# GameIT_HSRW.net
KiCad netlist of a schematic drawn in EAGLE
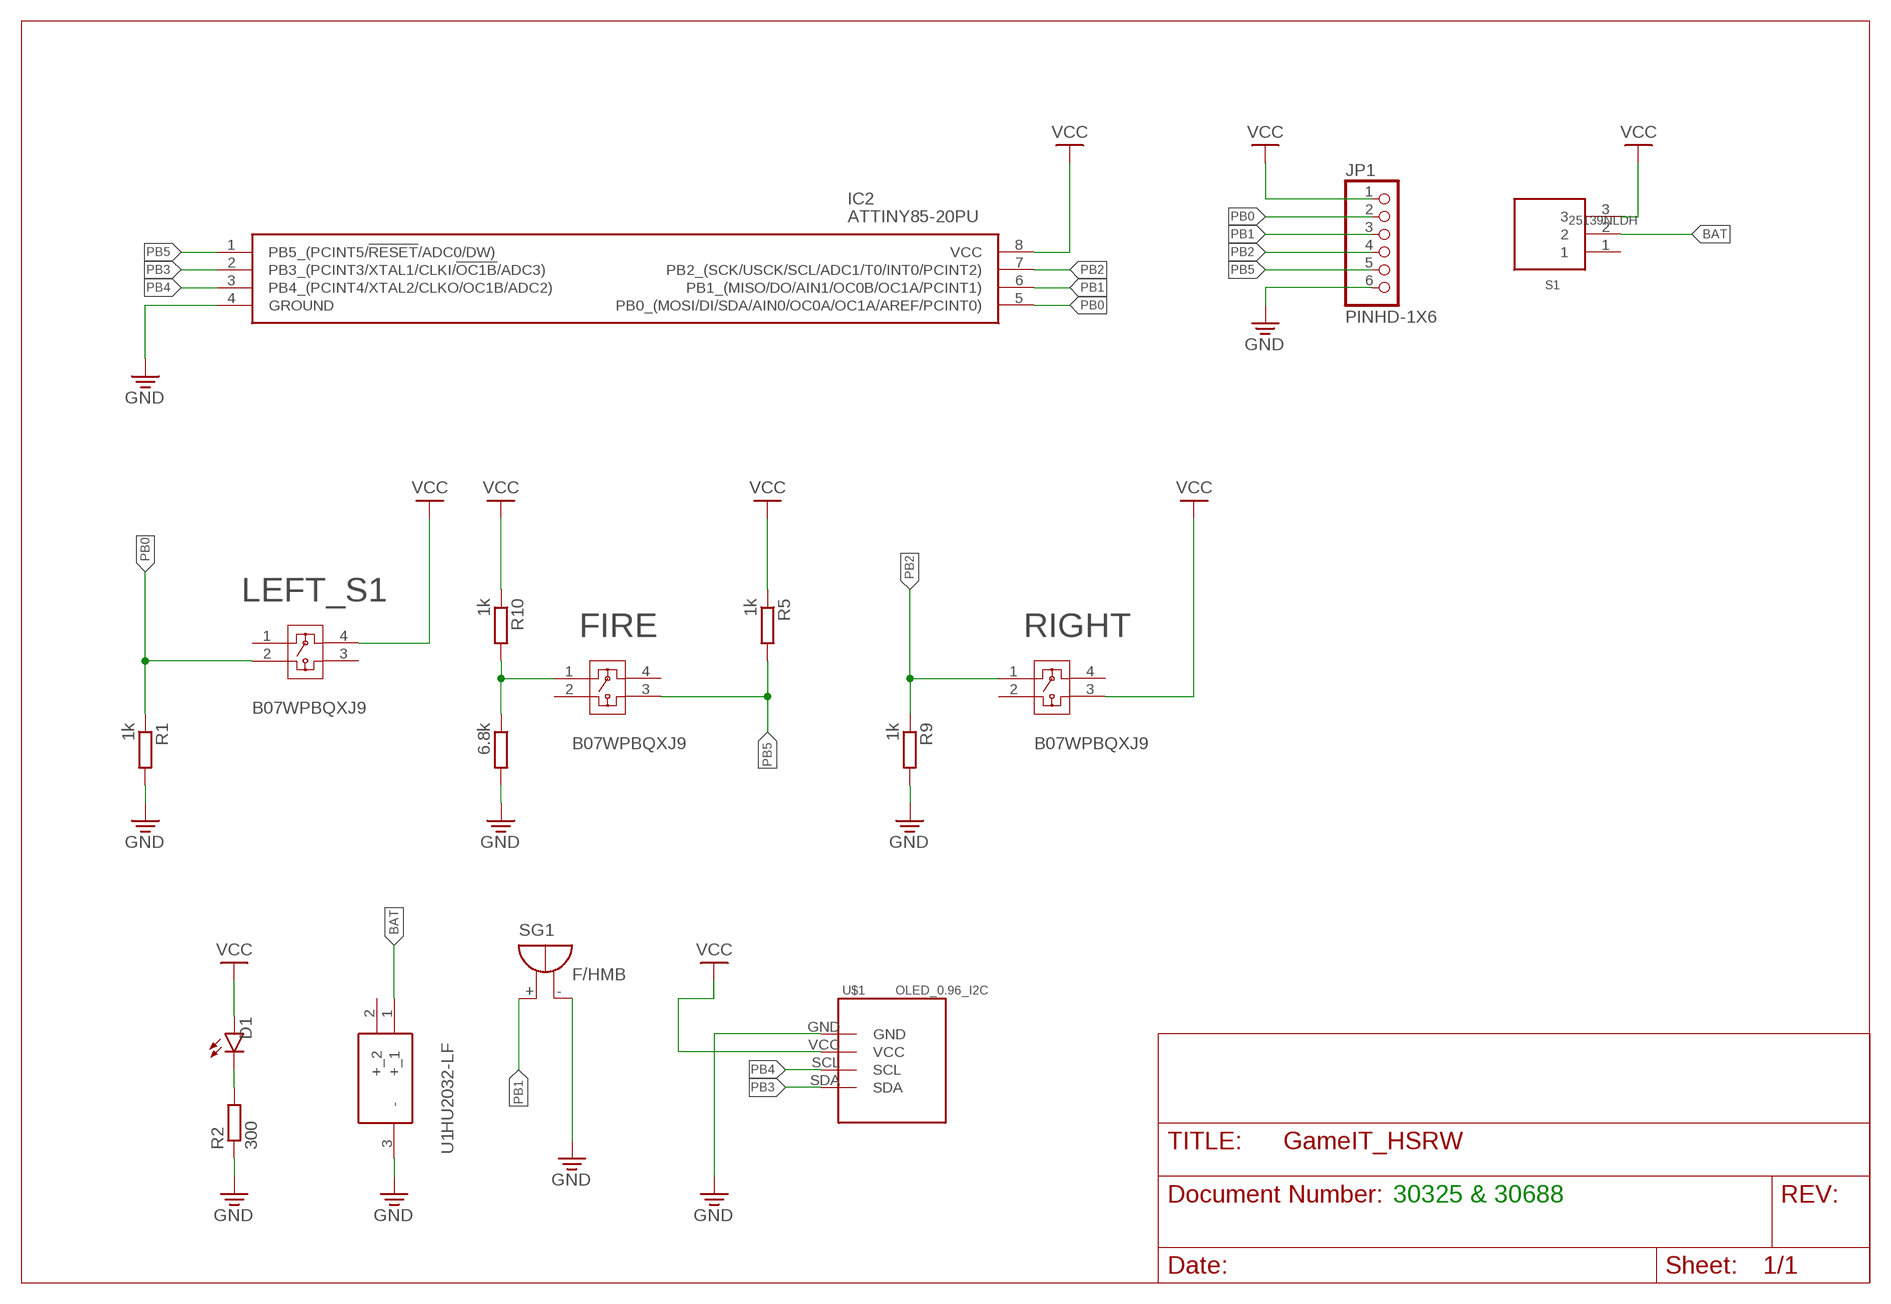
[diagram p0: schematic, sheet 1]

(export (version "E")
  (design (tool "Eeschema 10.0.6"))
  (components
    (comp (ref "D1")
      (value "LED_GREEN")
      (footprint "eagle-import:CHIPLED_1206")
      (libsource (lib "eagle-import") (part "LEDCHIPLED_1206"))
    )
    (comp (ref "FIRE")
      (value "COM-10302COM-10302_SPK")
      (footprint "eagle-import:COM-10302_SPK")
      (fields
        (field (name "MANUFACTURER_PART_NUMBER") "COM-10302")
        (field (name "COPYRIGHT") "Copyright (C) 2023 Ultra Librarian. All rights reserved.")
      )
      (libsource (lib "eagle-import") (part "COM-10302COM-10302_SPK"))
    )
    (comp (ref "IC2")
      (value "ATTINY85-20PU")
      (footprint "eagle-import:DIP781W56P254L950H533Q8N")
      (fields (field (name "MOUSER_PART_NUMBER") "556-ATTINY85-20PU"))
      (libsource (lib "eagle-import") (part "ATTINY85-20PU"))
    )
    (comp (ref "JP1")
      (value "PINHD-1X6")
      (footprint "eagle-import:1X06")
      (fields (field (name "MANUFACTURER") "Generic"))
      (libsource (lib "eagle-import") (part "PINHD-1X6"))
    )
    (comp (ref "LEFT_S1")
      (value "COM-10302COM-10302_SPK")
      (footprint "eagle-import:COM-10302_SPK")
      (fields
        (field (name "MANUFACTURER_PART_NUMBER") "COM-10302")
        (field (name "COPYRIGHT") "Copyright (C) 2023 Ultra Librarian. All rights reserved.")
      )
      (libsource (lib "eagle-import") (part "COM-10302COM-10302_SPK"))
    )
    (comp (ref "R1")
      (value "1k")
      (footprint "eagle-import:R1206")
      (libsource (lib "eagle-import") (part "R-EU_R1206"))
    )
    (comp (ref "R2")
      (value "300")
      (footprint "eagle-import:R1206")
      (libsource (lib "eagle-import") (part "R-EU_R1206"))
    )
    (comp (ref "R4")
      (value "6.8k")
      (footprint "eagle-import:R1206")
      (libsource (lib "eagle-import") (part "R-EU_R1206"))
    )
    (comp (ref "R5")
      (value "1k")
      (footprint "eagle-import:R1206")
      (libsource (lib "eagle-import") (part "R-EU_R1206"))
    )
    (comp (ref "R9")
      (value "1k")
      (footprint "eagle-import:R1206")
      (libsource (lib "eagle-import") (part "R-EU_R1206"))
    )
    (comp (ref "R10")
      (value "1k")
      (footprint "eagle-import:R1206")
      (libsource (lib "eagle-import") (part "R-EU_R1206"))
    )
    (comp (ref "RIGHT")
      (value "COM-10302COM-10302_SPK")
      (footprint "eagle-import:COM-10302_SPK")
      (fields
        (field (name "MANUFACTURER_PART_NUMBER") "COM-10302")
        (field (name "COPYRIGHT") "Copyright (C) 2023 Ultra Librarian. All rights reserved.")
      )
      (libsource (lib "eagle-import") (part "COM-10302COM-10302_SPK"))
    )
    (comp (ref "S1")
      (value "25139NLDH")
      (footprint "eagle-import:25139NLDH")
      (fields (field (name "MOUSER_PART_NUMBER") "642-25139NLDH"))
      (libsource (lib "eagle-import") (part "25139NLDH"))
    )
    (comp (ref "SG1")
      (value "F/HMB")
      (footprint "eagle-import:F_HMB")
      (libsource (lib "eagle-import") (part "F/HMB"))
    )
    (comp (ref "U$1")
      (value "OLED_0.96_I2C")
      (footprint "eagle-import:OLED_0.96_I2C")
      (libsource (lib "eagle-import") (part "OLED_0.96_I2C"))
    )
    (comp (ref "U1")
      (value "HU2032-LF")
      (footprint "eagle-import:HU2032LF")
      (fields (field (name "MOUSER_PART_NUMBER") "614-HU2032-LF"))
      (libsource (lib "eagle-import") (part "HU2032-LF"))
    )
  )
  (nets
    (net (code "1") (name "BAT") (class "Default")
      (node (ref "S1") (pin "2") (pinfunction "2_2") (pintype "bidirectional"))
      (node (ref "U1") (pin "1") (pinfunction "+_1_1") (pintype "bidirectional"))
    )
    (net (code "2") (name "GND") (class "Default")
      (node (ref "IC2") (pin "4") (pinfunction "GROUND_4") (pintype "power_in"))
      (node (ref "JP1") (pin "6") (pinfunction "6_6") (pintype "passive"))
      (node (ref "R1") (pin "2") (pinfunction "2_2") (pintype "passive"))
      (node (ref "R2") (pin "1") (pinfunction "1_1") (pintype "passive"))
      (node (ref "R4") (pin "2") (pinfunction "2_2") (pintype "passive"))
      (node (ref "R9") (pin "2") (pinfunction "2_2") (pintype "passive"))
      (node (ref "SG1") (pin "-") (pinfunction "-_-") (pintype "passive"))
      (node (ref "U$1") (pin "GND") (pinfunction "GND_GND") (pintype "bidirectional"))
      (node (ref "U1") (pin "3") (pinfunction "-_3") (pintype "bidirectional"))
    )
    (net (code "3") (name "Net-(D1-PadC)") (class "Default")
      (node (ref "D1") (pin "C") (pinfunction "C_C") (pintype "passive"))
      (node (ref "R2") (pin "2") (pinfunction "2_2") (pintype "passive"))
    )
    (net (code "4") (name "Net-(FIRE-Pad1)") (class "Default")
      (node (ref "FIRE") (pin "1") (pinfunction "1_1") (pintype "passive"))
      (node (ref "R10") (pin "2") (pinfunction "2_2") (pintype "passive"))
      (node (ref "R4") (pin "1") (pinfunction "1_1") (pintype "passive"))
    )
    (net (code "5") (name "PB0") (class "Default")
      (node (ref "IC2") (pin "5") (pinfunction "PB0_(MOSI/DI/SDA/AIN0/OC0A/OC1A/AREF/PCINT0)_5") (pintype "bidirectional"))
      (node (ref "JP1") (pin "2") (pinfunction "2_2") (pintype "passive"))
      (node (ref "LEFT_S1") (pin "2") (pinfunction "2_2") (pintype "passive"))
      (node (ref "R1") (pin "1") (pinfunction "1_1") (pintype "passive"))
    )
    (net (code "6") (name "PB1") (class "Default")
      (node (ref "IC2") (pin "6") (pinfunction "PB1_(MISO/DO/AIN1/OC0B/OC1A/PCINT1)_6") (pintype "bidirectional"))
      (node (ref "JP1") (pin "3") (pinfunction "3_3") (pintype "passive"))
      (node (ref "SG1") (pin "+") (pinfunction "+_+") (pintype "passive"))
    )
    (net (code "7") (name "PB2") (class "Default")
      (node (ref "IC2") (pin "7") (pinfunction "PB2_(SCK/USCK/SCL/ADC1/T0/INT0/PCINT2)_7") (pintype "bidirectional"))
      (node (ref "JP1") (pin "4") (pinfunction "4_4") (pintype "passive"))
      (node (ref "R9") (pin "1") (pinfunction "1_1") (pintype "passive"))
      (node (ref "RIGHT") (pin "1") (pinfunction "1_1") (pintype "passive"))
    )
    (net (code "8") (name "PB3") (class "Default")
      (node (ref "IC2") (pin "2") (pinfunction "PB3_(PCINT3/XTAL1/CLKI/~{OC1B}/ADC3)_2") (pintype "bidirectional"))
      (node (ref "U$1") (pin "SDA") (pinfunction "SDA_SDA") (pintype "bidirectional"))
    )
    (net (code "9") (name "PB4") (class "Default")
      (node (ref "IC2") (pin "3") (pinfunction "PB4_(PCINT4/XTAL2/CLKO/OC1B/ADC2)_3") (pintype "bidirectional"))
      (node (ref "U$1") (pin "SCL") (pinfunction "SCL_SCL") (pintype "bidirectional"))
    )
    (net (code "10") (name "PB5") (class "Default")
      (node (ref "FIRE") (pin "3") (pinfunction "3_3") (pintype "passive"))
      (node (ref "IC2") (pin "1") (pinfunction "PB5_(PCINT5/~{RESET}/ADC0/DW)_1") (pintype "bidirectional"))
      (node (ref "JP1") (pin "5") (pinfunction "5_5") (pintype "passive"))
      (node (ref "R5") (pin "2") (pinfunction "2_2") (pintype "passive"))
    )
    (net (code "11") (name "VCC") (class "Default")
      (node (ref "D1") (pin "A") (pinfunction "A_A") (pintype "passive"))
      (node (ref "IC2") (pin "8") (pinfunction "VCC_8") (pintype "power_in"))
      (node (ref "JP1") (pin "1") (pinfunction "1_1") (pintype "passive"))
      (node (ref "LEFT_S1") (pin "4") (pinfunction "4_4") (pintype "passive"))
      (node (ref "R10") (pin "1") (pinfunction "1_1") (pintype "passive"))
      (node (ref "R5") (pin "1") (pinfunction "1_1") (pintype "passive"))
      (node (ref "RIGHT") (pin "3") (pinfunction "3_3") (pintype "passive"))
      (node (ref "S1") (pin "3") (pinfunction "3_3") (pintype "bidirectional"))
      (node (ref "U$1") (pin "VCC") (pinfunction "VCC_VCC") (pintype "bidirectional"))
    )
    (net (code "12") (name "unconnected-(FIRE-Pad2)") (class "Default")
      (node (ref "FIRE") (pin "2") (pinfunction "2_2") (pintype "passive"))
    )
    (net (code "13") (name "unconnected-(FIRE-Pad4)") (class "Default")
      (node (ref "FIRE") (pin "4") (pinfunction "4_4") (pintype "passive"))
    )
    (net (code "14") (name "unconnected-(LEFT_S1-Pad1)") (class "Default")
      (node (ref "LEFT_S1") (pin "1") (pinfunction "1_1") (pintype "passive"))
    )
    (net (code "15") (name "unconnected-(LEFT_S1-Pad3)") (class "Default")
      (node (ref "LEFT_S1") (pin "3") (pinfunction "3_3") (pintype "passive"))
    )
    (net (code "16") (name "unconnected-(RIGHT-Pad2)") (class "Default")
      (node (ref "RIGHT") (pin "2") (pinfunction "2_2") (pintype "passive"))
    )
    (net (code "17") (name "unconnected-(RIGHT-Pad4)") (class "Default")
      (node (ref "RIGHT") (pin "4") (pinfunction "4_4") (pintype "passive"))
    )
    (net (code "18") (name "unconnected-(S1-Pad1)") (class "Default")
      (node (ref "S1") (pin "1") (pinfunction "1_1") (pintype "bidirectional"))
    )
    (net (code "19") (name "unconnected-(U1-+_2-Pad2)") (class "Default")
      (node (ref "U1") (pin "2") (pinfunction "+_2_2") (pintype "bidirectional"))
    )
  )
)
